# NU1680_Rx_EVM_SCH_Ver_2.net
KiCad netlist of a schematic drawn in Altium Designer
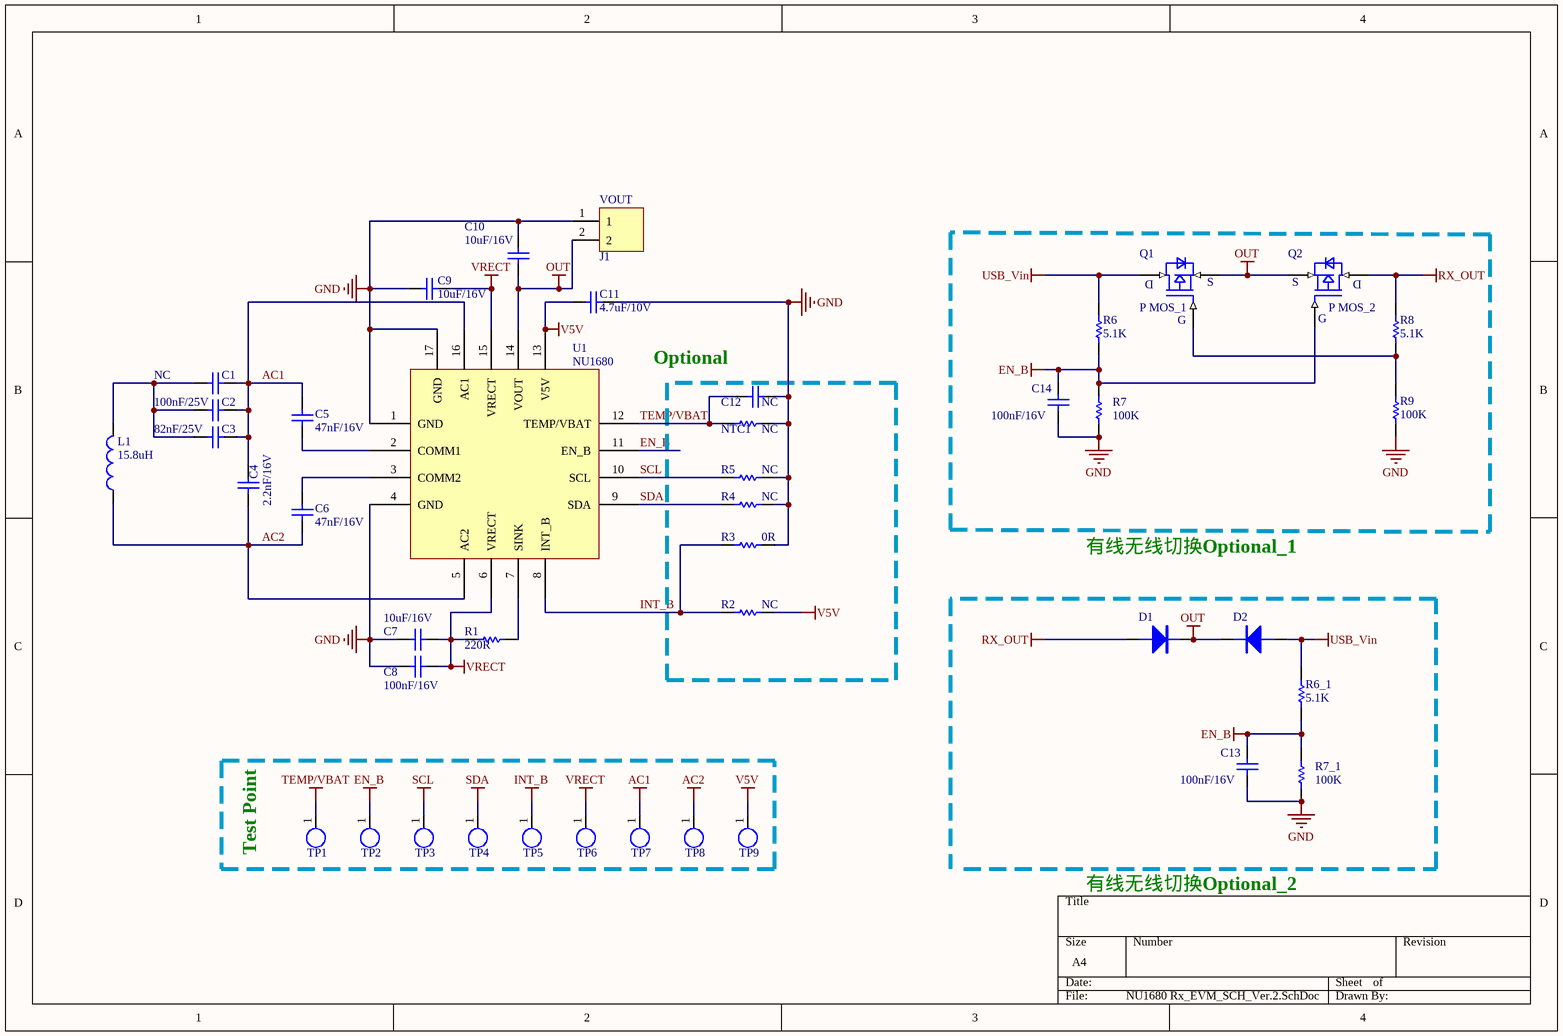
[diagram p0: NU1680 Rx_EVM_SCH_Ver.2.SchDoc]

(export (version "E")
  (design (tool "Eeschema 10.0.6"))
  (components
    (comp (ref "C1")
      (value "NC")
      (footprint "SMD_R5_CAP_0402")
      (description "0402")
      (libsource (lib "LL&S library") (part "cap"))
    )
    (comp (ref "C2")
      (value "100nF/25V")
      (footprint "SMD_R5_CAP_0402")
      (description "0402")
      (libsource (lib "LL&S library") (part "cap"))
    )
    (comp (ref "C3")
      (value "82nF/25V")
      (footprint "SMD_R5_CAP_0402")
      (description "0402")
      (libsource (lib "LL&S library") (part "cap"))
    )
    (comp (ref "C4")
      (value "2.2nF/16V")
      (footprint "SMD_R5_CAP_0402")
      (description "0402")
      (libsource (lib "LL&S library") (part "cap"))
    )
    (comp (ref "C5")
      (value "47nF/16V")
      (footprint "SMD_R5_CAP_0402")
      (description "0402")
      (libsource (lib "LL&S library") (part "cap"))
    )
    (comp (ref "C6")
      (value "47nF/16V")
      (footprint "SMD_R5_CAP_0402")
      (description "0402")
      (libsource (lib "LL&S library") (part "cap"))
    )
    (comp (ref "C7")
      (value "10uF/16V")
      (footprint "SMD_R5_CAP_0603")
      (description "0603")
      (libsource (lib "LL&S library") (part "cap"))
    )
    (comp (ref "C8")
      (value "100nF/16V")
      (footprint "SMD_R5_CAP_0402")
      (description "0402")
      (libsource (lib "LL&S library") (part "cap"))
    )
    (comp (ref "C9")
      (value "10uF/16V")
      (footprint "SMD_R5_CAP_0603")
      (description "0603")
      (libsource (lib "LL&S library") (part "cap"))
    )
    (comp (ref "C10")
      (value "10uF/16V")
      (footprint "SMD_R5_CAP_0603")
      (description "0603")
      (libsource (lib "LL&S library") (part "cap"))
    )
    (comp (ref "C11")
      (value "4.7uF/10V")
      (footprint "SMD_R5_CAP_0603")
      (description "0603")
      (libsource (lib "LL&S library") (part "cap"))
    )
    (comp (ref "C12")
      (value "NC")
      (footprint "SMD_R5_CAP_0402")
      (description "0402")
      (libsource (lib "LL&S library") (part "cap"))
    )
    (comp (ref "C13")
      (value "100nF/16V")
      (footprint "SMD_R5_CAP_0402")
      (description "0402")
      (libsource (lib "LL&S library") (part "cap"))
    )
    (comp (ref "C14")
      (value "100nF/16V")
      (footprint "SMD_R5_CAP_0402")
      (description "0402")
      (libsource (lib "LL&S library") (part "cap"))
    )
    (comp (ref "D1")
      (value "~")
      (footprint "DO-201AD(V)")
      (description "Diode")
      (libsource (lib "60W FAN6921MR LED Power schlib") (part "DIODE"))
    )
    (comp (ref "D2")
      (value "~")
      (footprint "DO-201AD(V)")
      (description "Diode")
      (libsource (lib "60W FAN6921MR LED Power schlib") (part "DIODE"))
    )
    (comp (ref "L1") (value "15.8uH") (footprint "HDR1X2") (libsource (lib "LL&S library") (part "Inductor")))
    (comp (ref "NTC1")
      (value "NC")
      (footprint "SMD_R5_RES_0402")
      (description "0402")
      (libsource (lib "LL&S library") (part "Res1"))
    )
    (comp (ref "Q1") (value "P MOS_1") (libsource (lib "60W FAN6921MR LED Power schlib") (part "P MOS_1")))
    (comp (ref "Q2") (value "P MOS_2") (libsource (lib "60W FAN6921MR LED Power schlib") (part "P MOS_2")))
    (comp (ref "R1")
      (value "220R")
      (footprint "SMD_R5_RES_0805")
      (description "0805")
      (libsource (lib "LL&S library") (part "Res1"))
    )
    (comp (ref "R2")
      (value "NC")
      (footprint "SMD_R5_RES_0402")
      (description "0402")
      (libsource (lib "LL&S library") (part "Res1"))
    )
    (comp (ref "R3")
      (value "0R")
      (footprint "SMD_R5_RES_0402")
      (description "0402")
      (libsource (lib "LL&S library") (part "Res1"))
    )
    (comp (ref "R4")
      (value "NC")
      (footprint "SMD_R5_RES_0402")
      (description "0402")
      (libsource (lib "LL&S library") (part "Res1"))
    )
    (comp (ref "R5")
      (value "NC")
      (footprint "SMD_R5_RES_0402")
      (description "0402")
      (libsource (lib "LL&S library") (part "Res1"))
    )
    (comp (ref "R6")
      (value "5.1K")
      (footprint "IR0402(R)")
      (description "RES 1.8Kohm 1/16W 1% 0402")
      (fields (field (name "Comment") "1.8K/5%/0402") (field (name "PUBLISHER") "Altium Limited"))
      (libsource (lib "PCB_Project1") (part "Res1"))
    )
    (comp (ref "R6_1")
      (value "5.1K")
      (footprint "IR0402(R)")
      (description "RES 1.8Kohm 1/16W 1% 0402")
      (fields (field (name "Comment") "1.8K/5%/0402") (field (name "PUBLISHER") "Altium Limited"))
      (libsource (lib "PCB_Project1") (part "Res1"))
    )
    (comp (ref "R7")
      (value "100K")
      (footprint "IR0402(R)")
      (description "RES 1.8Kohm 1/16W 1% 0402")
      (fields (field (name "Comment") "1.8K/5%/0402") (field (name "PUBLISHER") "Altium Limited"))
      (libsource (lib "PCB_Project1") (part "Res1"))
    )
    (comp (ref "R7_1")
      (value "100K")
      (footprint "IR0402(R)")
      (description "RES 1.8Kohm 1/16W 1% 0402")
      (fields (field (name "Comment") "1.8K/5%/0402") (field (name "PUBLISHER") "Altium Limited"))
      (libsource (lib "PCB_Project1") (part "Res1"))
    )
    (comp (ref "R8")
      (value "5.1K")
      (footprint "IR0402(R)")
      (description "RES 1.8Kohm 1/16W 1% 0402")
      (fields (field (name "Comment") "1.8K/5%/0402") (field (name "PUBLISHER") "Altium Limited"))
      (libsource (lib "PCB_Project1") (part "Res1"))
    )
    (comp (ref "R9")
      (value "100K")
      (footprint "IR0402(R)")
      (description "RES 1.8Kohm 1/16W 1% 0402")
      (fields (field (name "Comment") "1.8K/5%/0402") (field (name "PUBLISHER") "Altium Limited"))
      (libsource (lib "PCB_Project1") (part "Res1"))
    )
    (comp (ref "TP1")
      (value "~")
      (footprint "SMD_R5_Testpoint_1.5mm")
      (libsource (lib "LL&S library") (part "Testpoint"))
    )
    (comp (ref "TP2")
      (value "~")
      (footprint "SMD_R5_Testpoint_1.5mm")
      (libsource (lib "LL&S library") (part "Testpoint"))
    )
    (comp (ref "TP3")
      (value "~")
      (footprint "SMD_R5_Testpoint_1.5mm")
      (libsource (lib "LL&S library") (part "Testpoint"))
    )
    (comp (ref "TP4")
      (value "~")
      (footprint "SMD_R5_Testpoint_1.5mm")
      (libsource (lib "LL&S library") (part "Testpoint"))
    )
    (comp (ref "TP5")
      (value "~")
      (footprint "SMD_R5_Testpoint_1.5mm")
      (libsource (lib "LL&S library") (part "Testpoint"))
    )
    (comp (ref "TP6")
      (value "~")
      (footprint "SMD_R5_Testpoint_1.5mm")
      (libsource (lib "LL&S library") (part "Testpoint"))
    )
    (comp (ref "TP7")
      (value "~")
      (footprint "SMD_R5_Testpoint_1.5mm")
      (libsource (lib "LL&S library") (part "Testpoint"))
    )
    (comp (ref "TP8")
      (value "~")
      (footprint "SMD_R5_Testpoint_1.5mm")
      (libsource (lib "LL&S library") (part "Testpoint"))
    )
    (comp (ref "TP9")
      (value "~")
      (footprint "SMD_R5_Testpoint_1.5mm")
      (libsource (lib "LL&S library") (part "Testpoint"))
    )
    (comp (ref "U1")
      (value "NU1680")
      (footprint "NU1680_QFN16")
      (libsource (lib "LZJ_Schlib") (part "NU1680"))
    )
    (comp (ref "VOUT") (value "J1") (libsource (lib "LL&S library") (part "CONNECT2X1")))
  )
  (nets
    (net (code "1") (name "AC1") (class "Default")
      (node (ref "C1") (pin "2") (pinfunction "2_2") (pintype "passive"))
      (node (ref "C2") (pin "2") (pinfunction "2_2") (pintype "passive"))
      (node (ref "C3") (pin "2") (pinfunction "2_2") (pintype "passive"))
      (node (ref "C4") (pin "2") (pinfunction "2_2") (pintype "passive"))
      (node (ref "C5") (pin "1") (pinfunction "1_1") (pintype "passive"))
      (node (ref "TP7") (pin "1") (pinfunction "1_1") (pintype "passive"))
      (node (ref "U1") (pin "16") (pinfunction "AC1_16") (pintype "passive"))
    )
    (net (code "2") (name "AC2") (class "Default")
      (node (ref "C4") (pin "1") (pinfunction "1_1") (pintype "passive"))
      (node (ref "C6") (pin "1") (pinfunction "1_1") (pintype "passive"))
      (node (ref "L1") (pin "1") (pinfunction "1_1") (pintype "passive"))
      (node (ref "TP8") (pin "1") (pinfunction "1_1") (pintype "passive"))
      (node (ref "U1") (pin "5") (pinfunction "AC2_5") (pintype "passive"))
    )
    (net (code "3") (name "EN_B") (class "Default")
      (node (ref "C13") (pin "1") (pinfunction "1_1") (pintype "passive"))
      (node (ref "C14") (pin "1") (pinfunction "1_1") (pintype "passive"))
      (node (ref "Q2") (pin "1") (pinfunction "G_1") (pintype "input"))
      (node (ref "R6") (pin "1") (pinfunction "1_1") (pintype "passive"))
      (node (ref "R6_1") (pin "1") (pinfunction "1_1") (pintype "passive"))
      (node (ref "R7") (pin "2") (pinfunction "2_2") (pintype "passive"))
      (node (ref "R7_1") (pin "2") (pinfunction "2_2") (pintype "passive"))
      (node (ref "TP2") (pin "1") (pinfunction "1_1") (pintype "passive"))
      (node (ref "U1") (pin "11") (pinfunction "EN_B_11") (pintype "passive"))
    )
    (net (code "4") (name "GND") (class "Default")
      (node (ref "C10") (pin "2") (pinfunction "2_2") (pintype "passive"))
      (node (ref "C11") (pin "2") (pinfunction "2_2") (pintype "passive"))
      (node (ref "C12") (pin "1") (pinfunction "1_1") (pintype "passive"))
      (node (ref "C13") (pin "2") (pinfunction "2_2") (pintype "passive"))
      (node (ref "C14") (pin "2") (pinfunction "2_2") (pintype "passive"))
      (node (ref "C7") (pin "2") (pinfunction "2_2") (pintype "passive"))
      (node (ref "C8") (pin "2") (pinfunction "2_2") (pintype "passive"))
      (node (ref "C9") (pin "2") (pinfunction "2_2") (pintype "passive"))
      (node (ref "NTC1") (pin "1") (pinfunction "1_1") (pintype "passive"))
      (node (ref "R3") (pin "2") (pinfunction "2_2") (pintype "passive"))
      (node (ref "R4") (pin "1") (pinfunction "1_1") (pintype "passive"))
      (node (ref "R5") (pin "1") (pinfunction "1_1") (pintype "passive"))
      (node (ref "R7") (pin "1") (pinfunction "1_1") (pintype "passive"))
      (node (ref "R7_1") (pin "1") (pinfunction "1_1") (pintype "passive"))
      (node (ref "R9") (pin "2") (pinfunction "2_2") (pintype "passive"))
      (node (ref "U1") (pin "1") (pinfunction "GND_1") (pintype "passive"))
      (node (ref "U1") (pin "17") (pinfunction "GND_17") (pintype "passive"))
      (node (ref "U1") (pin "4") (pinfunction "GND_4") (pintype "passive"))
      (node (ref "VOUT") (pin "1") (pinfunction "1_1") (pintype "passive"))
    )
    (net (code "5") (name "INT_B") (class "Default")
      (node (ref "R2") (pin "1") (pinfunction "1_1") (pintype "passive"))
      (node (ref "R3") (pin "1") (pinfunction "1_1") (pintype "passive"))
      (node (ref "TP5") (pin "1") (pinfunction "1_1") (pintype "passive"))
      (node (ref "U1") (pin "8") (pinfunction "INT_B_8") (pintype "passive"))
    )
    (net (code "6") (name "Net-(C1-Pad1)") (class "Default")
      (node (ref "C1") (pin "1") (pinfunction "1_1") (pintype "passive"))
      (node (ref "C2") (pin "1") (pinfunction "1_1") (pintype "passive"))
      (node (ref "C3") (pin "1") (pinfunction "1_1") (pintype "passive"))
      (node (ref "L1") (pin "2") (pinfunction "2_2") (pintype "passive"))
    )
    (net (code "7") (name "Net-(Q1-G)") (class "Default")
      (node (ref "Q1") (pin "1") (pinfunction "G_1") (pintype "input"))
      (node (ref "R8") (pin "2") (pinfunction "2_2") (pintype "passive"))
      (node (ref "R9") (pin "1") (pinfunction "1_1") (pintype "passive"))
    )
    (net (code "8") (name "Net-(U1-COMM1)") (class "Default")
      (node (ref "C5") (pin "2") (pinfunction "2_2") (pintype "passive"))
      (node (ref "U1") (pin "2") (pinfunction "COMM1_2") (pintype "passive"))
    )
    (net (code "9") (name "Net-(U1-COMM2)") (class "Default")
      (node (ref "C6") (pin "2") (pinfunction "2_2") (pintype "passive"))
      (node (ref "U1") (pin "3") (pinfunction "COMM2_3") (pintype "passive"))
    )
    (net (code "10") (name "Net-(U1-SINK)") (class "Default")
      (node (ref "R1") (pin "1") (pinfunction "1_1") (pintype "passive"))
      (node (ref "U1") (pin "7") (pinfunction "SINK_7") (pintype "passive"))
    )
    (net (code "11") (name "OUT") (class "Default")
      (node (ref "C10") (pin "1") (pinfunction "1_1") (pintype "passive"))
      (node (ref "D1") (pin "2") (pinfunction "K_2") (pintype "passive"))
      (node (ref "D2") (pin "2") (pinfunction "K_2") (pintype "passive"))
      (node (ref "Q1") (pin "3") (pinfunction "S_3") (pintype "input"))
      (node (ref "Q2") (pin "2") (pinfunction "D_2") (pintype "input"))
      (node (ref "U1") (pin "14") (pinfunction "VOUT_14") (pintype "passive"))
      (node (ref "VOUT") (pin "2") (pinfunction "2_2") (pintype "passive"))
    )
    (net (code "12") (name "RX_OUT") (class "Default")
      (node (ref "D1") (pin "1") (pinfunction "A_1") (pintype "passive"))
      (node (ref "Q2") (pin "3") (pinfunction "S_3") (pintype "input"))
      (node (ref "R8") (pin "1") (pinfunction "1_1") (pintype "passive"))
    )
    (net (code "13") (name "SCL") (class "Default")
      (node (ref "R5") (pin "2") (pinfunction "2_2") (pintype "passive"))
      (node (ref "TP3") (pin "1") (pinfunction "1_1") (pintype "passive"))
      (node (ref "U1") (pin "10") (pinfunction "SCL_10") (pintype "passive"))
    )
    (net (code "14") (name "SDA") (class "Default")
      (node (ref "R4") (pin "2") (pinfunction "2_2") (pintype "passive"))
      (node (ref "TP4") (pin "1") (pinfunction "1_1") (pintype "passive"))
      (node (ref "U1") (pin "9") (pinfunction "SDA_9") (pintype "passive"))
    )
    (net (code "15") (name "TEMP{slash}VBAT") (class "Default")
      (node (ref "C12") (pin "2") (pinfunction "2_2") (pintype "passive"))
      (node (ref "NTC1") (pin "2") (pinfunction "2_2") (pintype "passive"))
      (node (ref "TP1") (pin "1") (pinfunction "1_1") (pintype "passive"))
      (node (ref "U1") (pin "12") (pinfunction "TEMP/VBAT_12") (pintype "passive"))
    )
    (net (code "16") (name "USB_Vin") (class "Default")
      (node (ref "D2") (pin "1") (pinfunction "A_1") (pintype "passive"))
      (node (ref "Q1") (pin "2") (pinfunction "D_2") (pintype "input"))
      (node (ref "R6") (pin "2") (pinfunction "2_2") (pintype "passive"))
      (node (ref "R6_1") (pin "2") (pinfunction "2_2") (pintype "passive"))
    )
    (net (code "17") (name "V5V") (class "Default")
      (node (ref "C11") (pin "1") (pinfunction "1_1") (pintype "passive"))
      (node (ref "R2") (pin "2") (pinfunction "2_2") (pintype "passive"))
      (node (ref "TP9") (pin "1") (pinfunction "1_1") (pintype "passive"))
      (node (ref "U1") (pin "13") (pinfunction "V5V_13") (pintype "passive"))
    )
    (net (code "18") (name "VRECT") (class "Default")
      (node (ref "C7") (pin "1") (pinfunction "1_1") (pintype "passive"))
      (node (ref "C8") (pin "1") (pinfunction "1_1") (pintype "passive"))
      (node (ref "C9") (pin "1") (pinfunction "1_1") (pintype "passive"))
      (node (ref "R1") (pin "2") (pinfunction "2_2") (pintype "passive"))
      (node (ref "TP6") (pin "1") (pinfunction "1_1") (pintype "passive"))
      (node (ref "U1") (pin "15") (pinfunction "VRECT_15") (pintype "passive"))
      (node (ref "U1") (pin "6") (pinfunction "VRECT_6") (pintype "passive"))
    )
  )
)
